# lab2_zasetskiy_buck.net
KiCad netlist of a schematic drawn in Altium Designer
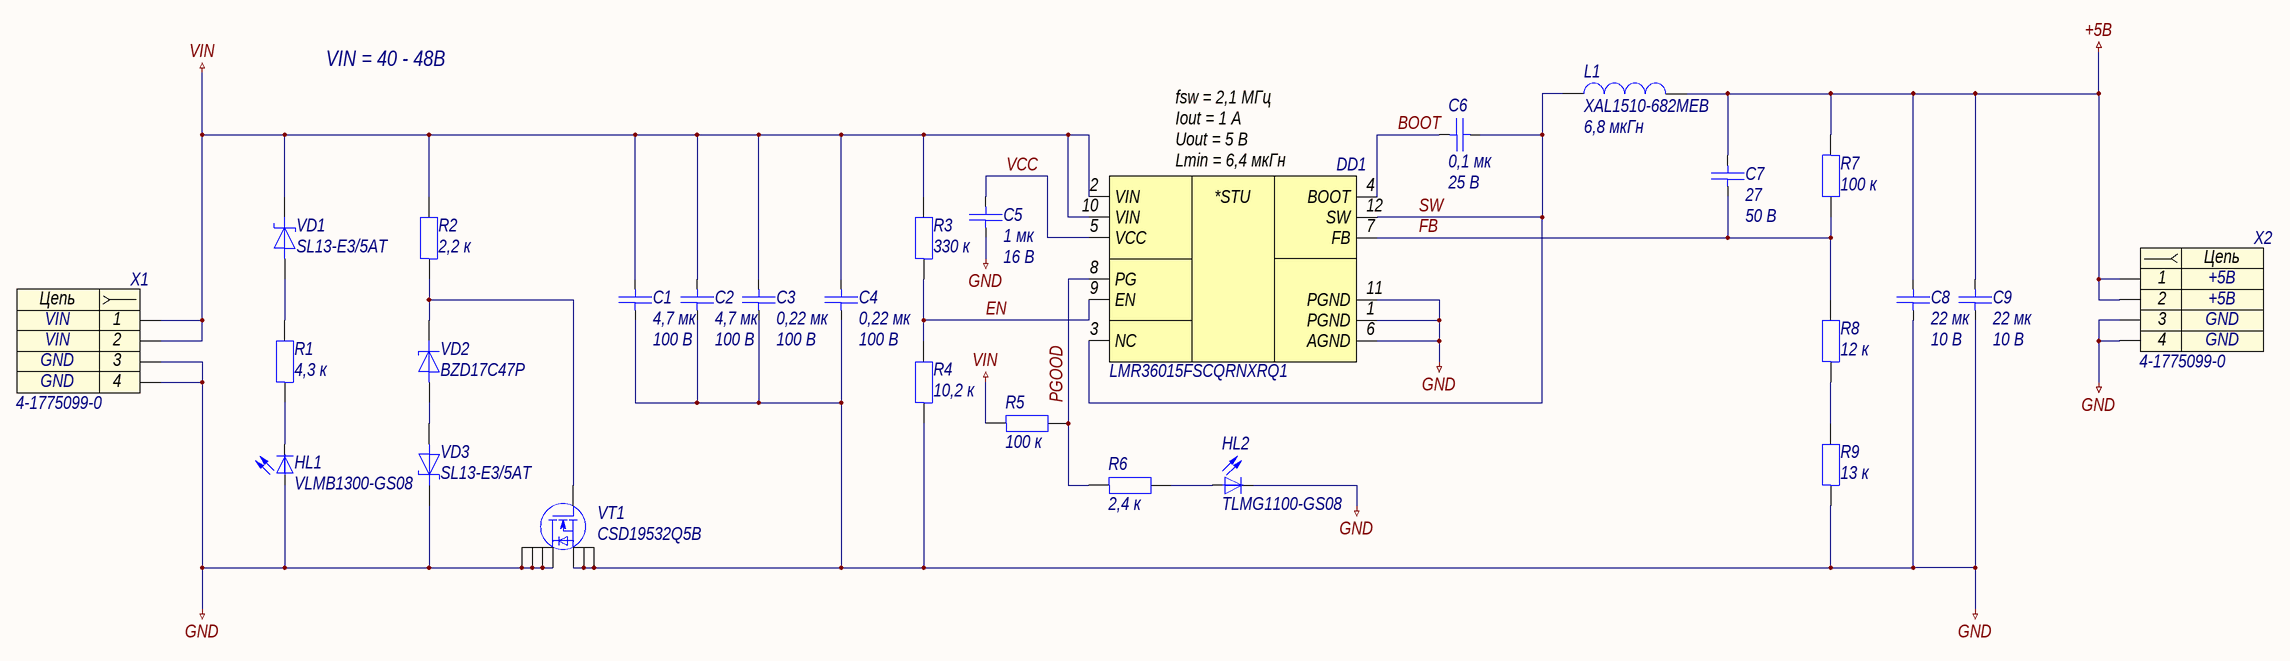
[diagram p0: lab2_zasetskiy_buck.SchDoc]

(export (version "E")
  (design (tool "Eeschema 10.0.6"))
  (components
    (comp (ref "C1")
      (value "4,7 мк")
      (footprint "C1210")
      (description "=Описание")
      (fields (field (name "НАПРЯЖЕНИЕ") "100 В"))
      (libsource (lib "Database_Students") (part "C-NONPOLAR"))
    )
    (comp (ref "C2")
      (value "4,7 мк")
      (footprint "C1210")
      (description "=Описание")
      (fields (field (name "НАПРЯЖЕНИЕ") "100 В"))
      (libsource (lib "Database_Students") (part "C-NONPOLAR"))
    )
    (comp (ref "C3")
      (value "0,22 мк")
      (footprint "C0805")
      (description "=Описание")
      (fields (field (name "НАПРЯЖЕНИЕ") "100 В"))
      (libsource (lib "Database_Students") (part "C-NONPOLAR"))
    )
    (comp (ref "C4")
      (value "0,22 мк")
      (footprint "C0805")
      (description "=Описание")
      (fields (field (name "НАПРЯЖЕНИЕ") "100 В"))
      (libsource (lib "Database_Students") (part "C-NONPOLAR"))
    )
    (comp (ref "C5")
      (value "1 мк")
      (footprint "C0603")
      (description "=Описание")
      (fields (field (name "НАПРЯЖЕНИЕ") "16 В"))
      (libsource (lib "Database_Students") (part "C-NONPOLAR"))
    )
    (comp (ref "C6")
      (value "0,1 мк")
      (footprint "C0603")
      (description "=Описание")
      (fields (field (name "НАПРЯЖЕНИЕ") "25 В"))
      (libsource (lib "Database_Students") (part "C-NONPOLAR"))
    )
    (comp (ref "C7")
      (value "27")
      (footprint "C0402")
      (description "=Описание")
      (fields (field (name "НАПРЯЖЕНИЕ") "50 В"))
      (libsource (lib "Database_Students") (part "C-NONPOLAR"))
    )
    (comp (ref "C8")
      (value "22 мк")
      (footprint "C1206")
      (description "=Описание")
      (fields (field (name "НАПРЯЖЕНИЕ") "10 В"))
      (libsource (lib "Database_Students") (part "C-NONPOLAR"))
    )
    (comp (ref "C9")
      (value "22 мк")
      (footprint "C1206")
      (description "=Описание")
      (fields (field (name "НАПРЯЖЕНИЕ") "10 В"))
      (libsource (lib "Database_Students") (part "C-NONPOLAR"))
    )
    (comp (ref "DD1")
      (value "LMR36015FSCQRNXRQ1")
      (footprint "VQFN-HR-12")
      (description "=Описание")
      (libsource (lib "Database_Students") (part "LMR36015FSCQRNXRQ1"))
    )
    (comp (ref "HL1")
      (value "VLMB1300-GS08")
      (footprint "LED")
      (description "=Описание")
      (libsource (lib "MyDatabase") (part "led"))
    )
    (comp (ref "HL2")
      (value "TLMG1100-GS08")
      (footprint "LED_GREEN")
      (description "=Описание")
      (libsource (lib "MyDatabase") (part "led"))
    )
    (comp (ref "L1")
      (value "XAL1510-682MEB")
      (footprint "XAL-2-1620X1520X1100")
      (description "=Описание")
      (fields (field (name "ИНДУКТИВНОСТЬ") "6,8 мкГн"))
      (libsource (lib "Database_Students") (part "INDUCTOR-COMMON"))
    )
    (comp (ref "R1")
      (value "4,3 к")
      (footprint "R0603")
      (description "=Описание")
      (libsource (lib "Database_Students") (part "R-COMMON"))
    )
    (comp (ref "R2")
      (value "2,2 к")
      (footprint "R0603")
      (description "=Описание")
      (libsource (lib "Database_Students") (part "R-COMMON"))
    )
    (comp (ref "R3")
      (value "330 к")
      (footprint "R0603")
      (description "=Описание")
      (libsource (lib "Database_Students") (part "R-COMMON"))
    )
    (comp (ref "R4")
      (value "10,2 к")
      (footprint "R0603")
      (description "=Описание")
      (libsource (lib "Database_Students") (part "R-COMMON"))
    )
    (comp (ref "R5")
      (value "100 к")
      (footprint "R0603")
      (description "=Описание")
      (libsource (lib "Database_Students") (part "R-COMMON"))
    )
    (comp (ref "R6")
      (value "2,4 к")
      (footprint "R0603")
      (description "=Описание")
      (libsource (lib "Database_Students") (part "R-COMMON"))
    )
    (comp (ref "R7")
      (value "100 к")
      (footprint "R0603")
      (description "=Описание")
      (libsource (lib "Database_Students") (part "R-COMMON"))
    )
    (comp (ref "R8")
      (value "12 к")
      (footprint "R0603")
      (description "=Описание")
      (libsource (lib "Database_Students") (part "R-COMMON"))
    )
    (comp (ref "R9")
      (value "13 к")
      (footprint "R0603")
      (description "=Описание")
      (libsource (lib "Database_Students") (part "R-COMMON"))
    )
    (comp (ref "VD1")
      (value "SL13-E3/5AT")
      (footprint "DO-214AC")
      (description "=Описание")
      (libsource (lib "Database_Students") (part "DIODE-SCHOTTKY"))
    )
    (comp (ref "VD2")
      (value "BZD17C47P")
      (footprint "DO-219AB")
      (description "=Описание")
      (libsource (lib "Database_Students") (part "ZENER-DIODE"))
    )
    (comp (ref "VD3")
      (value "SL13-E3/5AT")
      (footprint "DO-214AC")
      (description "=Описание")
      (libsource (lib "Database_Students") (part "DIODE-SCHOTTKY"))
    )
    (comp (ref "VT1")
      (value "CSD19532Q5B")
      (footprint "SON-8")
      (description "=Описание")
      (libsource (lib "Database_Students") (part "MOSFET-N-1G-3S-4D"))
    )
    (comp (ref "X1")
      (value "4-1775099-0")
      (footprint "4-1775099-0")
      (description "=Описание")
      (libsource (lib "") (part "HEADER-4-SCT_1"))
    )
    (comp (ref "X2")
      (value "4-1775099-0")
      (footprint "4-1775099-0")
      (description "=Описание")
      (libsource (lib "Database_Students") (part "HEADER-4-SCT"))
    )
  )
  (nets
    (net (code "1") (name "+5В") (class "Default")
      (node (ref "C7") (pin "1") (pinfunction "1_1") (pintype "passive"))
      (node (ref "C8") (pin "1") (pinfunction "1_1") (pintype "passive"))
      (node (ref "C9") (pin "1") (pinfunction "1_1") (pintype "passive"))
      (node (ref "L1") (pin "2") (pinfunction "2_2") (pintype "passive"))
      (node (ref "R7") (pin "1") (pinfunction "1_1") (pintype "passive"))
      (node (ref "X2") (pin "1") (pinfunction "1_1") (pintype "passive"))
      (node (ref "X2") (pin "2") (pinfunction "2_2") (pintype "passive"))
    )
    (net (code "2") (name "/BOOT") (class "Default")
      (node (ref "C6") (pin "2") (pinfunction "2_2") (pintype "passive"))
      (node (ref "DD1") (pin "4") (pinfunction "BOOT_4") (pintype "passive"))
    )
    (net (code "3") (name "/EN") (class "Default")
      (node (ref "DD1") (pin "9") (pinfunction "EN_9") (pintype "passive"))
      (node (ref "R3") (pin "1") (pinfunction "1_1") (pintype "passive"))
      (node (ref "R4") (pin "2") (pinfunction "2_2") (pintype "passive"))
    )
    (net (code "4") (name "/FB") (class "Default")
      (node (ref "C7") (pin "2") (pinfunction "2_2") (pintype "passive"))
      (node (ref "DD1") (pin "7") (pinfunction "FB_7") (pintype "passive"))
      (node (ref "R7") (pin "2") (pinfunction "2_2") (pintype "passive"))
      (node (ref "R8") (pin "2") (pinfunction "2_2") (pintype "passive"))
    )
    (net (code "5") (name "/PGOOD") (class "Default")
      (node (ref "DD1") (pin "8") (pinfunction "PG_8") (pintype "passive"))
      (node (ref "R5") (pin "2") (pinfunction "2_2") (pintype "passive"))
      (node (ref "R6") (pin "1") (pinfunction "1_1") (pintype "passive"))
    )
    (net (code "6") (name "/SW") (class "Default")
      (node (ref "C6") (pin "1") (pinfunction "1_1") (pintype "passive"))
      (node (ref "DD1") (pin "12") (pinfunction "SW_12") (pintype "passive"))
      (node (ref "DD1") (pin "3") (pinfunction "NC_3") (pintype "passive"))
      (node (ref "L1") (pin "1") (pinfunction "1_1") (pintype "passive"))
    )
    (net (code "7") (name "/VCC") (class "Default")
      (node (ref "C5") (pin "1") (pinfunction "1_1") (pintype "passive"))
      (node (ref "DD1") (pin "5") (pinfunction "VCC_5") (pintype "passive"))
    )
    (net (code "8") (name "GND") (class "Default")
      (node (ref "C1") (pin "2") (pinfunction "2_2") (pintype "passive"))
      (node (ref "C2") (pin "2") (pinfunction "2_2") (pintype "passive"))
      (node (ref "C3") (pin "2") (pinfunction "2_2") (pintype "passive"))
      (node (ref "C4") (pin "2") (pinfunction "2_2") (pintype "passive"))
      (node (ref "C5") (pin "2") (pinfunction "2_2") (pintype "passive"))
      (node (ref "C8") (pin "2") (pinfunction "2_2") (pintype "passive"))
      (node (ref "C9") (pin "2") (pinfunction "2_2") (pintype "passive"))
      (node (ref "DD1") (pin "1") (pinfunction "PGND_1") (pintype "passive"))
      (node (ref "DD1") (pin "11") (pinfunction "PGND_11") (pintype "passive"))
      (node (ref "DD1") (pin "6") (pinfunction "AGND_6") (pintype "passive"))
      (node (ref "HL1") (pin "1") (pinfunction "A_1") (pintype "passive"))
      (node (ref "HL2") (pin "2") (pinfunction "K_2") (pintype "passive"))
      (node (ref "R4") (pin "1") (pinfunction "1_1") (pintype "passive"))
      (node (ref "R9") (pin "1") (pinfunction "1_1") (pintype "passive"))
      (node (ref "VD3") (pin "1") (pinfunction "1_1") (pintype "passive"))
      (node (ref "VT1") (pin "D") (pinfunction "D_D") (pintype "passive"))
      (node (ref "VT1") (pin "S") (pinfunction "S_S") (pintype "passive"))
      (node (ref "X1") (pin "3") (pinfunction "3_3") (pintype "passive"))
      (node (ref "X1") (pin "4") (pinfunction "4_4") (pintype "passive"))
      (node (ref "X2") (pin "3") (pinfunction "3_3") (pintype "passive"))
      (node (ref "X2") (pin "4") (pinfunction "4_4") (pintype "passive"))
    )
    (net (code "9") (name "Net-(HL1-K)") (class "Default")
      (node (ref "HL1") (pin "2") (pinfunction "K_2") (pintype "passive"))
      (node (ref "R1") (pin "1") (pinfunction "1_1") (pintype "passive"))
    )
    (net (code "10") (name "Net-(HL2-A)") (class "Default")
      (node (ref "HL2") (pin "1") (pinfunction "A_1") (pintype "passive"))
      (node (ref "R6") (pin "2") (pinfunction "2_2") (pintype "passive"))
    )
    (net (code "11") (name "Net-(R1-Pad2)") (class "Default")
      (node (ref "R1") (pin "2") (pinfunction "2_2") (pintype "passive"))
      (node (ref "VD1") (pin "2") (pinfunction "2_2") (pintype "passive"))
    )
    (net (code "12") (name "Net-(R2-Pad1)") (class "Default")
      (node (ref "R2") (pin "1") (pinfunction "1_1") (pintype "passive"))
      (node (ref "VD2") (pin "1") (pinfunction "1_1") (pintype "passive"))
      (node (ref "VT1") (pin "G") (pinfunction "G_G") (pintype "passive"))
    )
    (net (code "13") (name "Net-(R8-Pad1)") (class "Default")
      (node (ref "R8") (pin "1") (pinfunction "1_1") (pintype "passive"))
      (node (ref "R9") (pin "2") (pinfunction "2_2") (pintype "passive"))
    )
    (net (code "14") (name "Net-(VD2-Pad2)") (class "Default")
      (node (ref "VD2") (pin "2") (pinfunction "2_2") (pintype "passive"))
      (node (ref "VD3") (pin "2") (pinfunction "2_2") (pintype "passive"))
    )
    (net (code "15") (name "VIN") (class "Default")
      (node (ref "C1") (pin "1") (pinfunction "1_1") (pintype "passive"))
      (node (ref "C2") (pin "1") (pinfunction "1_1") (pintype "passive"))
      (node (ref "C3") (pin "1") (pinfunction "1_1") (pintype "passive"))
      (node (ref "C4") (pin "1") (pinfunction "1_1") (pintype "passive"))
      (node (ref "DD1") (pin "10") (pinfunction "VIN_10") (pintype "passive"))
      (node (ref "DD1") (pin "2") (pinfunction "VIN_2") (pintype "passive"))
      (node (ref "R2") (pin "2") (pinfunction "2_2") (pintype "passive"))
      (node (ref "R3") (pin "2") (pinfunction "2_2") (pintype "passive"))
      (node (ref "R5") (pin "1") (pinfunction "1_1") (pintype "passive"))
      (node (ref "VD1") (pin "1") (pinfunction "1_1") (pintype "passive"))
      (node (ref "X1") (pin "1") (pinfunction "1_1") (pintype "passive"))
      (node (ref "X1") (pin "2") (pinfunction "2_2") (pintype "passive"))
    )
  )
)
